# jalase2.net
KiCad netlist of a schematic drawn in Altium Designer
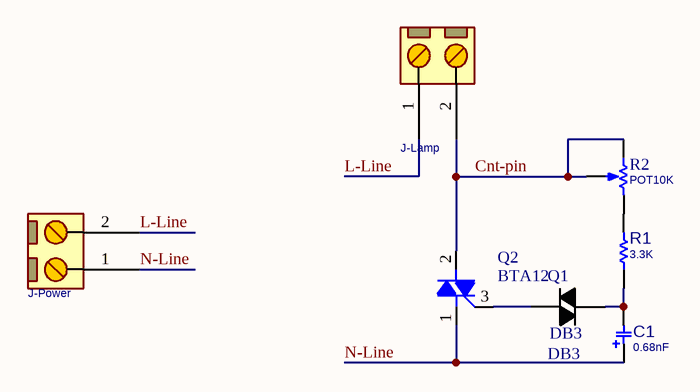
[diagram p0: jalase2.SchDoc]

(export (version "E")
  (design (tool "Eeschema 10.0.6"))
  (components
    (comp (ref "C1")
      (value "0.68nF")
      (footprint "C_FLM_7X5H11")
      (description "CAP, THD, FILM,")
      (fields (field (name "MANF_P#") "MANF_PART#") (field (name "MANF") "MANF"))
      (libsource (lib "passive_thd") (part "CAP_THD_FLM"))
    )
    (comp (ref "J-Lamp")
      (value "CONN_TB2")
      (footprint "MSTB_2")
      (description "CONN, PHOENIX MSTB, 5-G, 5.08mm pitch")
      (libsource (lib "") (part "CONN_MSTB_2_1"))
    )
    (comp (ref "J-Power")
      (value "CONN_TB2")
      (footprint "MSTB_2")
      (description "CONN, PHOENIX MSTB, 5-G, 5.08mm pitch")
      (libsource (lib "conn_terminalB") (part "CONN_MSTB_2"))
    )
    (comp (ref "Q1")
      (value "DB3")
      (footprint "D_AX03_DO35")
      (description "Diac, 32VBO, DO-35")
      (fields (field (name "MANF") "ST") (field (name "ALTIUM_VALUE") "DB3"))
      (libsource (lib "triac_diac") (part "DIAC_DB3_DO35"))
    )
    (comp (ref "Q2")
      (value "BTA12")
      (footprint "TO220_3")
      (description "Triac, 600V, 12A, TO-220")
      (fields (field (name "MANF_P#") "BTA12-600BW, BTA12-600CW, BTA12-600TW") (field (name "MANF") "ST"))
      (libsource (lib "triac_diac") (part "TRIAC_BTA12-600_TO220"))
    )
    (comp (ref "R1")
      (value "3.3K")
      (footprint "R025W_AX04")
      (description "RESISTOR, THD")
      (fields (field (name "MANF_P#") "RK73H1ETTP4701F") (field (name "MANF") "KOA SPEER"))
      (libsource (lib "passive_thd") (part "RES_THD"))
    )
    (comp (ref "R2")
      (value "POT10K")
      (footprint "VOL_R")
      (description "RESISTOR, THD, Potentiometer Volume")
      (libsource (lib "resistor_pot_trimmer") (part "RES_THD_POT_VOL"))
    )
  )
  (nets
    (net (code "1") (name "/Cnt-pin") (class "Default")
      (node (ref "J-Lamp") (pin "2") (pinfunction "2_2") (pintype "passive"))
      (node (ref "Q2") (pin "2") (pinfunction "T2_2") (pintype "passive"))
      (node (ref "R2") (pin "1") (pinfunction "TOP_1") (pintype "passive"))
      (node (ref "R2") (pin "2") (pinfunction "TAP_2") (pintype "passive"))
    )
    (net (code "2") (name "/L-Line") (class "Default")
      (node (ref "J-Lamp") (pin "1") (pinfunction "1_1") (pintype "passive"))
      (node (ref "J-Power") (pin "2") (pinfunction "2_2") (pintype "passive"))
    )
    (net (code "3") (name "/N-Line") (class "Default")
      (node (ref "C1") (pin "1") (pinfunction "1_1") (pintype "passive"))
      (node (ref "J-Power") (pin "1") (pinfunction "1_1") (pintype "passive"))
      (node (ref "Q2") (pin "1") (pinfunction "T1_1") (pintype "passive"))
    )
    (net (code "4") (name "Net-(Q1-A1)") (class "Default")
      (node (ref "Q1") (pin "1") (pinfunction "A1_1") (pintype "passive"))
      (node (ref "Q2") (pin "3") (pinfunction "G_3") (pintype "passive"))
    )
    (net (code "5") (name "Net-(Q1-A2)") (class "Default")
      (node (ref "C1") (pin "2") (pinfunction "2_2") (pintype "passive"))
      (node (ref "Q1") (pin "2") (pinfunction "A2_2") (pintype "passive"))
      (node (ref "R1") (pin "1") (pinfunction "1_1") (pintype "passive"))
    )
    (net (code "6") (name "Net-(R2-BOT)") (class "Default")
      (node (ref "R1") (pin "2") (pinfunction "2_2") (pintype "passive"))
      (node (ref "R2") (pin "3") (pinfunction "BOT_3") (pintype "passive"))
    )
  )
)
